# SheetV1.net
KiCad netlist of a schematic drawn in Altium Designer
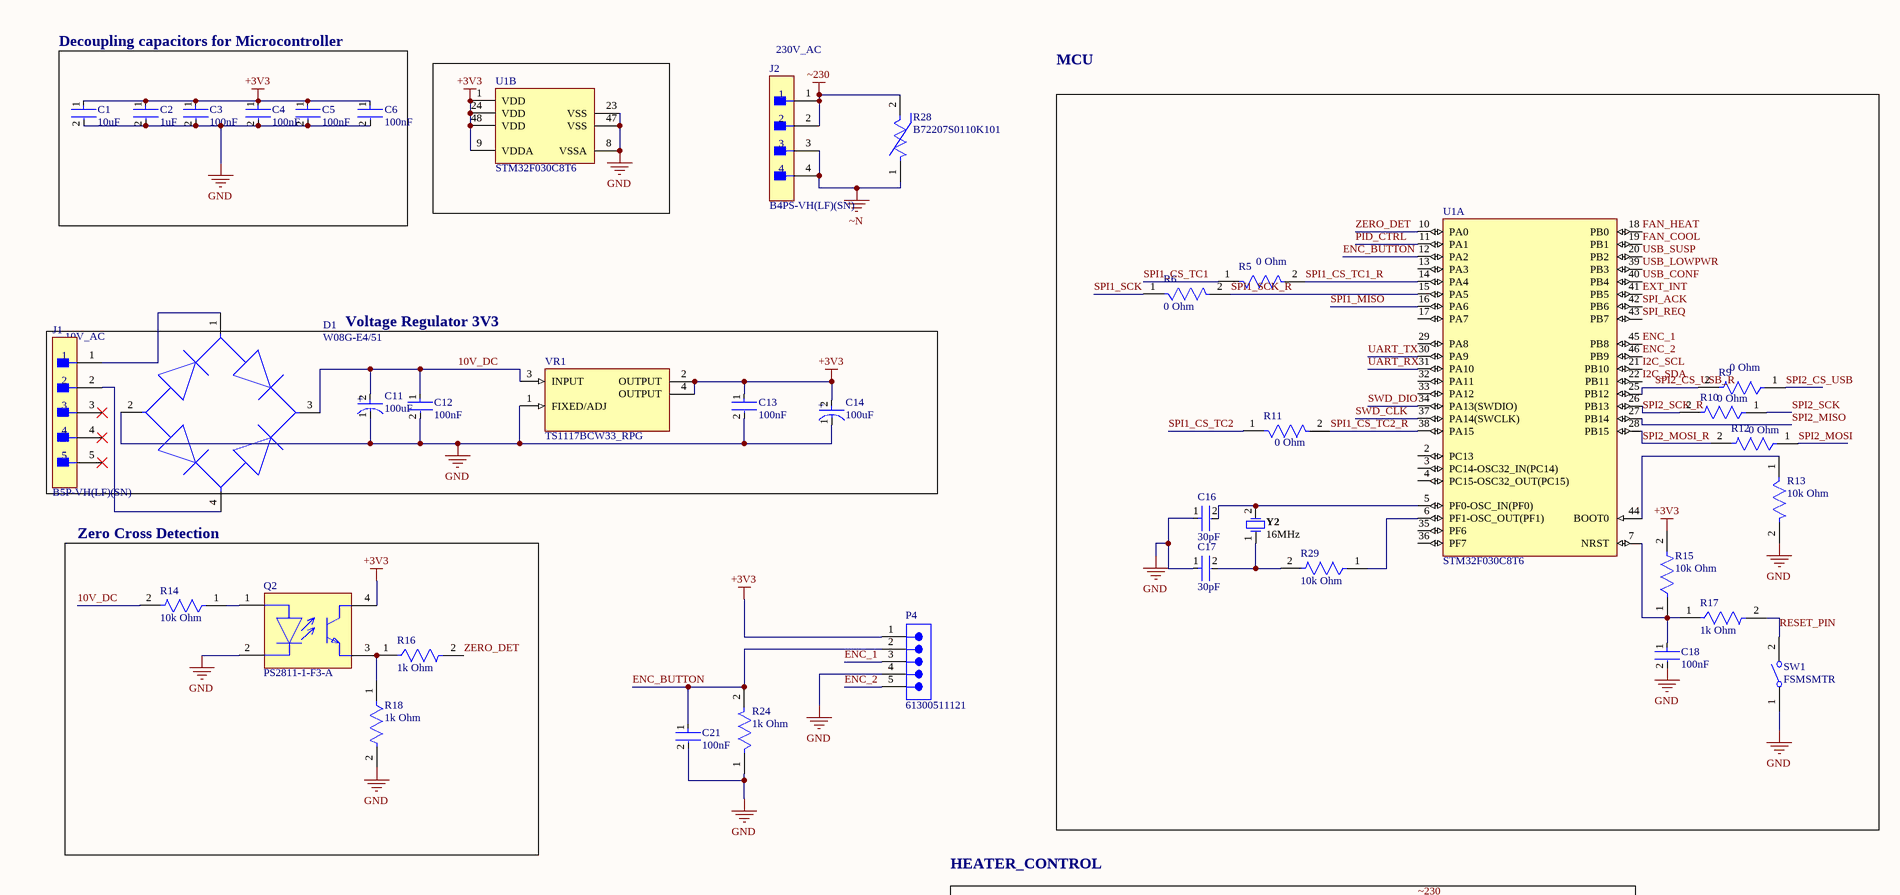
[diagram p0: SheetV1.SchDoc, top left]
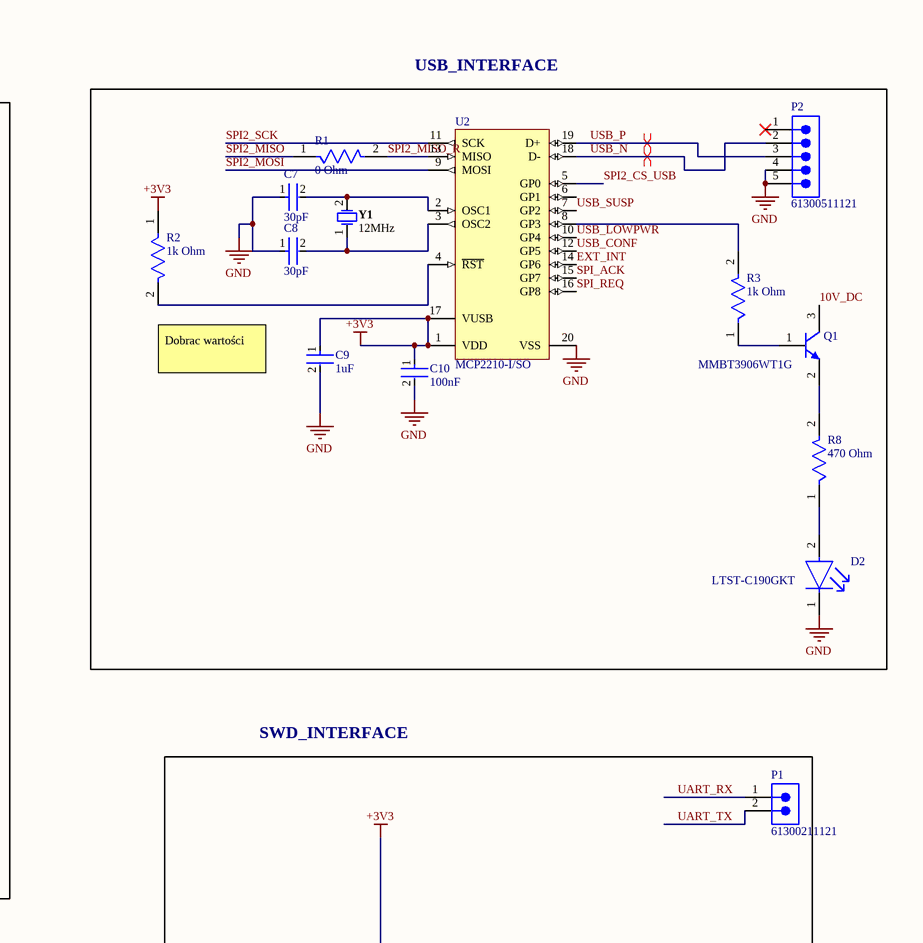
[diagram p1: SheetV1.SchDoc, top right]
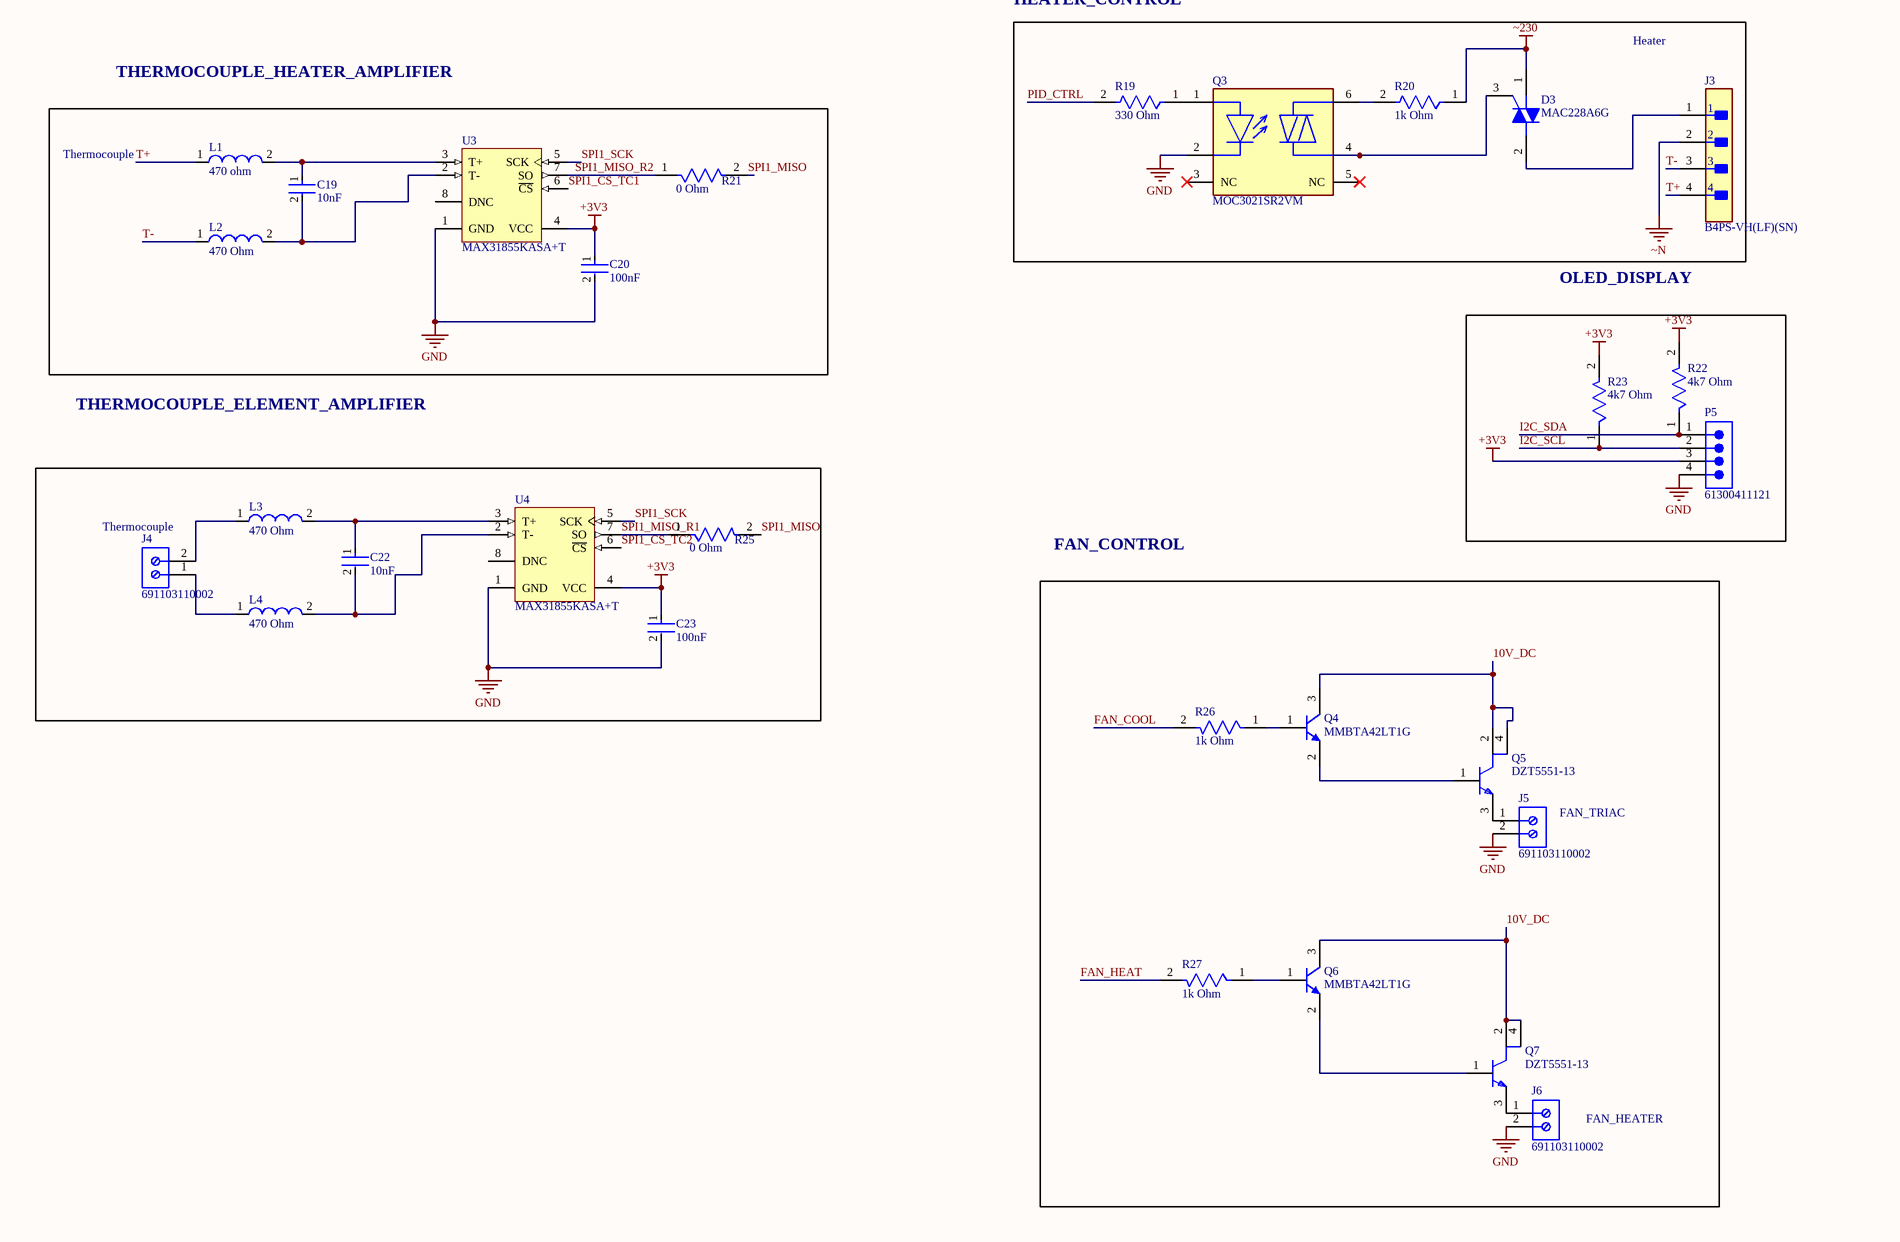
[diagram p2: SheetV1.SchDoc, bottom left]
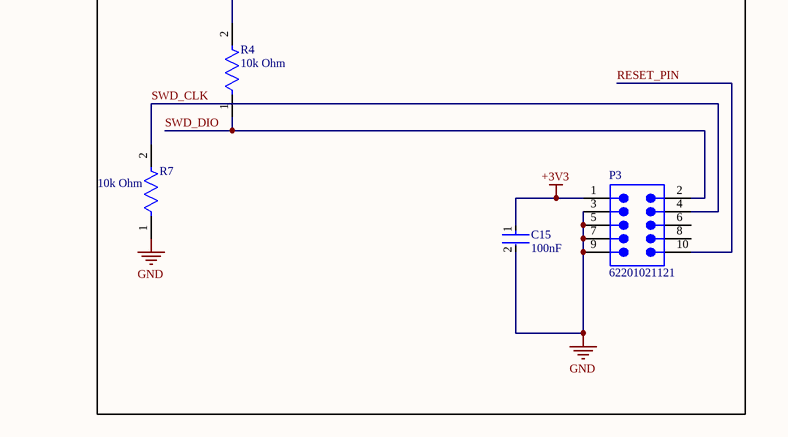
[diagram p3: SheetV1.SchDoc, bottom right]

(export (version "E")
  (design (tool "Eeschema 10.0.6"))
  (components
    (comp (ref "C1")
      (value "10uF")
      (footprint "FP-CC0805-0_85-MFG")
      (description "CAP CER 0.1UF 50V X7R 0805")
      (fields (field (name "TOLERANCE") "0.1") (field (name "MANUFACTURER PART NUMBER") "CC0805KRX7R9BB104"))
      (libsource (lib "Altium Content Vault") (part "11868f565c42a9108669ba33697ecf6"))
    )
    (comp (ref "C2")
      (value "1uF")
      (footprint "FP-CC0805-0_85-MFG")
      (description "CAP CER 0.1UF 50V X7R 0805")
      (fields (field (name "TOLERANCE") "0.1") (field (name "MANUFACTURER PART NUMBER") "CC0805KRX7R9BB104"))
      (libsource (lib "Altium Content Vault") (part "11868f565c42a9108669ba33697ecf6"))
    )
    (comp (ref "C3")
      (value "100nF")
      (footprint "FP-CC0805-0_85-MFG")
      (description "CAP CER 0.1UF 50V X7R 0805")
      (fields (field (name "TOLERANCE") "0.1") (field (name "MANUFACTURER PART NUMBER") "CC0805KRX7R9BB104"))
      (libsource (lib "Altium Content Vault") (part "11868f565c42a9108669ba33697ecf6"))
    )
    (comp (ref "C4")
      (value "100nF")
      (footprint "FP-CC0805-0_85-MFG")
      (description "CAP CER 0.1UF 50V X7R 0805")
      (fields (field (name "TOLERANCE") "0.1") (field (name "MANUFACTURER PART NUMBER") "CC0805KRX7R9BB104"))
      (libsource (lib "Altium Content Vault") (part "11868f565c42a9108669ba33697ecf6"))
    )
    (comp (ref "C5")
      (value "100nF")
      (footprint "FP-CC0805-0_85-MFG")
      (description "CAP CER 0.1UF 50V X7R 0805")
      (fields (field (name "TOLERANCE") "0.1") (field (name "MANUFACTURER PART NUMBER") "CC0805KRX7R9BB104"))
      (libsource (lib "Altium Content Vault") (part "11868f565c42a9108669ba33697ecf6"))
    )
    (comp (ref "C6")
      (value "100nF")
      (footprint "FP-CC0805-0_85-MFG")
      (description "CAP CER 0.1UF 50V X7R 0805")
      (fields (field (name "TOLERANCE") "0.1") (field (name "MANUFACTURER PART NUMBER") "CC0805KRX7R9BB104"))
      (libsource (lib "Altium Content Vault") (part "11868f565c42a9108669ba33697ecf6"))
    )
    (comp (ref "C7")
      (value "30pF")
      (footprint "FP-CC0805-0_85-MFG")
      (description "CAP CER 0.1UF 50V X7R 0805")
      (fields (field (name "TOLERANCE") "0.1") (field (name "MANUFACTURER PART NUMBER") "CC0805KRX7R9BB104"))
      (libsource (lib "Altium Content Vault") (part "11868f565c42a9108669ba33697ecf6"))
    )
    (comp (ref "C8")
      (value "30pF")
      (footprint "FP-CC0805-0_85-MFG")
      (description "CAP CER 0.1UF 50V X7R 0805")
      (fields (field (name "TOLERANCE") "0.1") (field (name "MANUFACTURER PART NUMBER") "CC0805KRX7R9BB104"))
      (libsource (lib "Altium Content Vault") (part "11868f565c42a9108669ba33697ecf6"))
    )
    (comp (ref "C9")
      (value "1uF")
      (footprint "FP-CC0805-0_85-MFG")
      (description "CAP CER 0.1UF 50V X7R 0805")
      (fields (field (name "TOLERANCE") "0.1") (field (name "MANUFACTURER PART NUMBER") "CC0805KRX7R9BB104"))
      (libsource (lib "Altium Content Vault") (part "11868f565c42a9108669ba33697ecf6"))
    )
    (comp (ref "C10")
      (value "100nF")
      (footprint "FP-CC0805-0_85-MFG")
      (description "CAP CER 0.1UF 50V X7R 0805")
      (fields (field (name "TOLERANCE") "0.1") (field (name "MANUFACTURER PART NUMBER") "CC0805KRX7R9BB104"))
      (libsource (lib "Altium Content Vault") (part "11868f565c42a9108669ba33697ecf6"))
    )
    (comp (ref "C11")
      (value "100uF")
      (footprint "FP-RAD-TH-D_10_0_5-L_12_5-MFG")
      (description "Aluminum Electrolytic Capacitors (Radial Lead Type) 3.3uF ±20% 400V")
      (fields (field (name "TOLERANCE") "20%") (field (name "VOLTAGE") "400V"))
      (libsource (lib "Altium Content Vault") (part "203bc49f2ac43e59fd269a8c329ed05"))
    )
    (comp (ref "C12")
      (value "100nF")
      (footprint "FP-CC0805-0_85-MFG")
      (description "CAP CER 0.1UF 50V X7R 0805")
      (fields (field (name "TOLERANCE") "0.1") (field (name "MANUFACTURER PART NUMBER") "CC0805KRX7R9BB104"))
      (libsource (lib "Altium Content Vault") (part "11868f565c42a9108669ba33697ecf6"))
    )
    (comp (ref "C13")
      (value "100nF")
      (footprint "FP-CC0805-0_85-MFG")
      (description "CAP CER 0.1UF 50V X7R 0805")
      (fields (field (name "TOLERANCE") "0.1") (field (name "MANUFACTURER PART NUMBER") "CC0805KRX7R9BB104"))
      (libsource (lib "Altium Content Vault") (part "11868f565c42a9108669ba33697ecf6"))
    )
    (comp (ref "C14")
      (value "100uF")
      (footprint "FP-RAD-TH-D_10_0_5-L_12_5-MFG")
      (description "Aluminum Electrolytic Capacitors (Radial Lead Type) 3.3uF ±20% 400V")
      (fields (field (name "TOLERANCE") "20%") (field (name "VOLTAGE") "400V"))
      (libsource (lib "Altium Content Vault") (part "203bc49f2ac43e59fd269a8c329ed05"))
    )
    (comp (ref "C15")
      (value "100nF")
      (footprint "FP-CC0805-0_85-MFG")
      (description "CAP CER 0.1UF 50V X7R 0805")
      (fields (field (name "TOLERANCE") "0.1") (field (name "MANUFACTURER PART NUMBER") "CC0805KRX7R9BB104"))
      (libsource (lib "Altium Content Vault") (part "11868f565c42a9108669ba33697ecf6"))
    )
    (comp (ref "C16")
      (value "30pF")
      (footprint "FP-CC0805-0_85-MFG")
      (description "CAP CER 0.1UF 50V X7R 0805")
      (fields (field (name "TOLERANCE") "0.1") (field (name "MANUFACTURER PART NUMBER") "CC0805KRX7R9BB104"))
      (libsource (lib "Altium Content Vault") (part "11868f565c42a9108669ba33697ecf6"))
    )
    (comp (ref "C17")
      (value "30pF")
      (footprint "FP-CC0805-0_85-MFG")
      (description "CAP CER 0.1UF 50V X7R 0805")
      (fields (field (name "TOLERANCE") "0.1") (field (name "MANUFACTURER PART NUMBER") "CC0805KRX7R9BB104"))
      (libsource (lib "Altium Content Vault") (part "11868f565c42a9108669ba33697ecf6"))
    )
    (comp (ref "C18")
      (value "100nF")
      (footprint "FP-CC0805-0_85-MFG")
      (description "CAP CER 0.1UF 50V X7R 0805")
      (fields (field (name "TOLERANCE") "0.1") (field (name "MANUFACTURER PART NUMBER") "CC0805KRX7R9BB104"))
      (libsource (lib "Altium Content Vault") (part "11868f565c42a9108669ba33697ecf6"))
    )
    (comp (ref "C19")
      (value "10nF")
      (footprint "FP-CC0805-0_85-MFG")
      (description "CAP CER 0.1UF 50V X7R 0805")
      (fields (field (name "TOLERANCE") "0.1") (field (name "MANUFACTURER PART NUMBER") "CC0805KRX7R9BB104"))
      (libsource (lib "Altium Content Vault") (part "11868f565c42a9108669ba33697ecf6"))
    )
    (comp (ref "C20")
      (value "100nF")
      (footprint "FP-CC0805-0_85-MFG")
      (description "CAP CER 0.1UF 50V X7R 0805")
      (fields (field (name "TOLERANCE") "0.1") (field (name "MANUFACTURER PART NUMBER") "CC0805KRX7R9BB104"))
      (libsource (lib "Altium Content Vault") (part "11868f565c42a9108669ba33697ecf6"))
    )
    (comp (ref "C21")
      (value "100nF")
      (footprint "FP-CC0805-0_85-MFG")
      (description "CAP CER 0.1UF 50V X7R 0805")
      (fields (field (name "TOLERANCE") "0.1") (field (name "MANUFACTURER PART NUMBER") "CC0805KRX7R9BB104"))
      (libsource (lib "Altium Content Vault") (part "11868f565c42a9108669ba33697ecf6"))
    )
    (comp (ref "C22")
      (value "10nF")
      (footprint "FP-CC0805-0_85-MFG")
      (description "CAP CER 0.1UF 50V X7R 0805")
      (fields (field (name "TOLERANCE") "0.1") (field (name "MANUFACTURER PART NUMBER") "CC0805KRX7R9BB104"))
      (libsource (lib "Altium Content Vault") (part "11868f565c42a9108669ba33697ecf6"))
    )
    (comp (ref "C23")
      (value "100nF")
      (footprint "FP-CC0805-0_85-MFG")
      (description "CAP CER 0.1UF 50V X7R 0805")
      (fields (field (name "TOLERANCE") "0.1") (field (name "MANUFACTURER PART NUMBER") "CC0805KRX7R9BB104"))
      (libsource (lib "Altium Content Vault") (part "11868f565c42a9108669ba33697ecf6"))
    )
    (comp (ref "D1")
      (value "W08G-E4/51")
      (footprint "FP-WOG-MFG")
      (description "W08G-E4/51 Diode Rectifier Bridge Single 800V 1.5A 4-Pin Case WOG Bulk")
      (libsource (lib "Altium Content Vault") (part "7f679ecdc54638986ed3433d0c5b104"))
    )
    (comp (ref "D2")
      (value "LTST-C190GKT")
      (footprint "FP-LTST-C190GKT-MFG")
      (description "LED GREEN CLEAR CHIP SMD")
      (fields (field (name "VOLTAGE") "2V"))
      (libsource (lib "Altium Content Vault") (part "8706943c75ba83719d021d2fdc84c58"))
    )
    (comp (ref "D3")
      (value "MAC228A6G")
      (footprint "ONSC-TO-220-3-221A-09")
      (description "Sensitive Gate Triacs, Silicon Bidirectional Thyristor, 3-Pin TO-220, Pb-Free, Bulk Box")
      (fields (field (name "MANUFACTURER") "On Semiconductor"))
      (libsource (lib "Altium Content Vault") (part "ONSC-TRIAC-MT1MT2G-3"))
    )
    (comp (ref "J1")
      (value "B5P-VH(LF)(SN)")
      (footprint "FP-B5P-VH_LF_SN-MFG")
      (description "CONN HEADER VERT 5POS 3.96MM")
      (libsource (lib "Altium Content Vault") (part "051ac7c1f60a91215dd69c4e70fad1a"))
    )
    (comp (ref "J2")
      (value "B4PS-VH(LF)(SN)")
      (footprint "FP-B4PS-VH_LF_SN-MFG")
      (description "CONN HEADER R/A 4POS 3.96MM")
      (libsource (lib "") (part "299a8cea1bdcbc3624fe62c390fa72c_1"))
    )
    (comp (ref "J3")
      (value "B4PS-VH(LF)(SN)")
      (footprint "FP-B4PS-VH_LF_SN-MFG")
      (description "CONN HEADER R/A 4POS 3.96MM")
      (libsource (lib "Altium Content Vault") (part "299a8cea1bdcbc3624fe62c390fa72c"))
    )
    (comp (ref "J4")
      (value "691103110002")
      (footprint "691103110002")
      (fields (field (name "VOLTAGE") "125V"))
      (libsource (lib "Altium Content Vault") (part "TBL - 1R - 02P - Screw"))
    )
    (comp (ref "J5")
      (value "691103110002")
      (footprint "691103110002")
      (fields (field (name "VOLTAGE") "125V"))
      (libsource (lib "Altium Content Vault") (part "TBL - 1R - 02P - Screw"))
    )
    (comp (ref "J6")
      (value "691103110002")
      (footprint "691103110002")
      (fields (field (name "VOLTAGE") "125V"))
      (libsource (lib "Altium Content Vault") (part "TBL - 1R - 02P - Screw"))
    )
    (comp (ref "L1")
      (value "470 ohm")
      (footprint "SMD-0805")
      (description "SMD EMI Suppression Ferrite Bead WE-CBF, Z = 470 Ohm")
      (libsource (lib "Altium Content Vault") (part "PAS-IND-INDUCTOR-2"))
    )
    (comp (ref "L2")
      (value "470 Ohm")
      (footprint "SMD-0805")
      (description "SMD EMI Suppression Ferrite Bead WE-CBF, Z = 470 Ohm")
      (libsource (lib "Altium Content Vault") (part "PAS-IND-INDUCTOR-2"))
    )
    (comp (ref "L3")
      (value "470 Ohm")
      (footprint "SMD-0805")
      (description "SMD EMI Suppression Ferrite Bead WE-CBF, Z = 470 Ohm")
      (libsource (lib "Altium Content Vault") (part "PAS-IND-INDUCTOR-2"))
    )
    (comp (ref "L4")
      (value "470 Ohm")
      (footprint "SMD-0805")
      (description "SMD EMI Suppression Ferrite Bead WE-CBF, Z = 470 Ohm")
      (libsource (lib "Altium Content Vault") (part "PAS-IND-INDUCTOR-2"))
    )
    (comp (ref "P1")
      (value "61300211121")
      (footprint "61300211121")
      (libsource (lib "Altium Content Vault") (part "Header_Male_1R_02P"))
    )
    (comp (ref "P2")
      (value "61300511121")
      (footprint "61300511121")
      (libsource (lib "Altium Content Vault") (part "Header_Male_1R_05P"))
    )
    (comp (ref "P3")
      (value "62201021121")
      (footprint "62201021121")
      (libsource (lib "Altium Content Vault") (part "Header_Male_2R_10P"))
    )
    (comp (ref "P4")
      (value "61300511121")
      (footprint "61300511121")
      (libsource (lib "Altium Content Vault") (part "Header_Male_1R_05P"))
    )
    (comp (ref "P5")
      (value "61300411121")
      (footprint "61300411121")
      (libsource (lib "Altium Content Vault") (part "Header_Male_1R_04P"))
    )
    (comp (ref "Q1")
      (value "MMBT3906WT1G")
      (footprint "ONSC-SC-70-3-419-04_V")
      (description "General Purpose Transistor, PNP Silicon, 3-Pin SC70, Pb-Free, Tape and Reel")
      (fields (field (name "MANUFACTURER") "On Semiconductor"))
      (libsource (lib "Altium Content Vault") (part "ONSC-NPN-B1E2C3-3"))
    )
    (comp (ref "Q2")
      (value "PS2811-1-F3-A")
      (footprint "SOP127P700X210_HS-5_SO4-Opto2_N")
      (description "Optocoupler DC-IN 1-CH Transistor DC-OUT 4-Pin SSOP Embossed T/R")
      (libsource (lib "Altium Content Vault") (part "f4732c5a005c16655bf03302f8bd1cc"))
    )
    (comp (ref "Q3")
      (value "MOC3021SR2VM")
      (footprint "FP-646BY-MFG")
      (description "MOC3021SR2VM Triac Driver Output Optocoupler, 6-Pin DIP 400V Random Phase")
      (libsource (lib "Altium Content Vault") (part "315d33d7a3de83856d3bd334bf87c2f"))
    )
    (comp (ref "Q4")
      (value "MMBTA42LT1G")
      (footprint "ONSC-SOT-23-3-318-08_V")
      (description "High Voltage Transistor, NPN Silicon, 3-Pin SOT-23, Pb-Free, Tape and Reel")
      (fields (field (name "MANUFACTURER") "On Semiconductor"))
      (libsource (lib "Altium Content Vault") (part "ONSC-NPN-B1E2C3-3"))
    )
    (comp (ref "Q5")
      (value "DZT5551-13")
      (footprint "FP-SOT223-MFG")
      (description "TRANS NPN 160V 0.6A SOT-223")
      (fields
        (field (name "MANUFACTURER") "Diodes")
        (field (name "OCTOPART") "https://octopart.com/dzt5551-13-diodes+inc.-12426785")
      )
      (libsource (lib "Altium Content Vault") (part "ef0222921274e2dfe3c88fb5f98777d"))
    )
    (comp (ref "Q6")
      (value "MMBTA42LT1G")
      (footprint "ONSC-SOT-23-3-318-08_V")
      (description "High Voltage Transistor, NPN Silicon, 3-Pin SOT-23, Pb-Free, Tape and Reel")
      (fields (field (name "MANUFACTURER") "On Semiconductor"))
      (libsource (lib "Altium Content Vault") (part "ONSC-NPN-B1E2C3-3"))
    )
    (comp (ref "Q7")
      (value "DZT5551-13")
      (footprint "FP-SOT223-MFG")
      (description "TRANS NPN 160V 0.6A SOT-223")
      (fields
        (field (name "MANUFACTURER") "Diodes")
        (field (name "OCTOPART") "https://octopart.com/dzt5551-13-diodes+inc.-12426785")
      )
      (libsource (lib "Altium Content Vault") (part "ef0222921274e2dfe3c88fb5f98777d"))
    )
    (comp (ref "R1")
      (value "0 Ohm")
      (footprint "FP-RMCF0805-MFG")
      (description "RES 0 OHM JUMPER 1/8W 0805")
      (libsource (lib "Altium Content Vault") (part "1029c3af85768c4190bb7ad29bc67b5"))
    )
    (comp (ref "R2")
      (value "1k Ohm")
      (footprint "FP-RMCF0805-MFG")
      (description "RES 0 OHM JUMPER 1/8W 0805")
      (libsource (lib "Altium Content Vault") (part "1029c3af85768c4190bb7ad29bc67b5"))
    )
    (comp (ref "R3")
      (value "1k Ohm")
      (footprint "FP-RMCF0805-MFG")
      (description "RES 0 OHM JUMPER 1/8W 0805")
      (libsource (lib "Altium Content Vault") (part "1029c3af85768c4190bb7ad29bc67b5"))
    )
    (comp (ref "R4")
      (value "10k Ohm")
      (footprint "FP-RMCF0805-MFG")
      (description "RES 0 OHM JUMPER 1/8W 0805")
      (libsource (lib "Altium Content Vault") (part "1029c3af85768c4190bb7ad29bc67b5"))
    )
    (comp (ref "R5")
      (value "0 Ohm")
      (footprint "FP-RMCF0805-MFG")
      (description "RES 0 OHM JUMPER 1/8W 0805")
      (libsource (lib "Altium Content Vault") (part "1029c3af85768c4190bb7ad29bc67b5"))
    )
    (comp (ref "R6")
      (value "0 Ohm")
      (footprint "FP-RMCF0805-MFG")
      (description "RES 0 OHM JUMPER 1/8W 0805")
      (libsource (lib "Altium Content Vault") (part "1029c3af85768c4190bb7ad29bc67b5"))
    )
    (comp (ref "R7")
      (value "10k Ohm")
      (footprint "FP-RMCF0805-MFG")
      (description "RES 0 OHM JUMPER 1/8W 0805")
      (libsource (lib "Altium Content Vault") (part "1029c3af85768c4190bb7ad29bc67b5"))
    )
    (comp (ref "R8")
      (value "470 Ohm")
      (footprint "FP-RMCF0805-MFG")
      (description "RES 0 OHM JUMPER 1/8W 0805")
      (libsource (lib "Altium Content Vault") (part "1029c3af85768c4190bb7ad29bc67b5"))
    )
    (comp (ref "R9")
      (value "0 Ohm")
      (footprint "FP-RMCF0805-MFG")
      (description "RES 0 OHM JUMPER 1/8W 0805")
      (libsource (lib "Altium Content Vault") (part "1029c3af85768c4190bb7ad29bc67b5"))
    )
    (comp (ref "R10")
      (value "0 Ohm")
      (footprint "FP-RMCF0805-MFG")
      (description "RES 0 OHM JUMPER 1/8W 0805")
      (libsource (lib "Altium Content Vault") (part "1029c3af85768c4190bb7ad29bc67b5"))
    )
    (comp (ref "R11")
      (value "0 Ohm")
      (footprint "FP-RMCF0805-MFG")
      (description "RES 0 OHM JUMPER 1/8W 0805")
      (libsource (lib "Altium Content Vault") (part "1029c3af85768c4190bb7ad29bc67b5"))
    )
    (comp (ref "R12")
      (value "0 Ohm")
      (footprint "FP-RMCF0805-MFG")
      (description "RES 0 OHM JUMPER 1/8W 0805")
      (libsource (lib "Altium Content Vault") (part "1029c3af85768c4190bb7ad29bc67b5"))
    )
    (comp (ref "R13")
      (value "10k Ohm")
      (footprint "FP-RMCF0805-MFG")
      (description "RES 0 OHM JUMPER 1/8W 0805")
      (libsource (lib "Altium Content Vault") (part "1029c3af85768c4190bb7ad29bc67b5"))
    )
    (comp (ref "R14")
      (value "10k Ohm")
      (footprint "FP-RMCF0805-MFG")
      (description "RES 0 OHM JUMPER 1/8W 0805")
      (libsource (lib "Altium Content Vault") (part "1029c3af85768c4190bb7ad29bc67b5"))
    )
    (comp (ref "R15")
      (value "10k Ohm")
      (footprint "FP-RMCF0805-MFG")
      (description "RES 0 OHM JUMPER 1/8W 0805")
      (libsource (lib "Altium Content Vault") (part "1029c3af85768c4190bb7ad29bc67b5"))
    )
    (comp (ref "R16")
      (value "1k Ohm")
      (footprint "FP-RMCF0805-MFG")
      (description "RES 0 OHM JUMPER 1/8W 0805")
      (libsource (lib "Altium Content Vault") (part "1029c3af85768c4190bb7ad29bc67b5"))
    )
    (comp (ref "R17")
      (value "1k Ohm")
      (footprint "FP-RMCF0805-MFG")
      (description "RES 0 OHM JUMPER 1/8W 0805")
      (libsource (lib "Altium Content Vault") (part "1029c3af85768c4190bb7ad29bc67b5"))
    )
    (comp (ref "R18")
      (value "1k Ohm")
      (footprint "FP-RMCF0805-MFG")
      (description "RES 0 OHM JUMPER 1/8W 0805")
      (libsource (lib "Altium Content Vault") (part "1029c3af85768c4190bb7ad29bc67b5"))
    )
    (comp (ref "R19")
      (value "330 Ohm")
      (footprint "FP-RMCF0805-MFG")
      (description "RES 0 OHM JUMPER 1/8W 0805")
      (libsource (lib "Altium Content Vault") (part "1029c3af85768c4190bb7ad29bc67b5"))
    )
    (comp (ref "R20")
      (value "1k Ohm")
      (footprint "FP-RMCF0805-MFG")
      (description "RES 0 OHM JUMPER 1/8W 0805")
      (libsource (lib "Altium Content Vault") (part "1029c3af85768c4190bb7ad29bc67b5"))
    )
    (comp (ref "R21")
      (value "0 Ohm")
      (footprint "FP-RMCF0805-MFG")
      (description "RES 0 OHM JUMPER 1/8W 0805")
      (libsource (lib "Altium Content Vault") (part "1029c3af85768c4190bb7ad29bc67b5"))
    )
    (comp (ref "R22")
      (value "4k7 Ohm")
      (footprint "FP-RMCF0805-MFG")
      (description "RES 0 OHM JUMPER 1/8W 0805")
      (libsource (lib "Altium Content Vault") (part "1029c3af85768c4190bb7ad29bc67b5"))
    )
    (comp (ref "R23")
      (value "4k7 Ohm")
      (footprint "FP-RMCF0805-MFG")
      (description "RES 0 OHM JUMPER 1/8W 0805")
      (libsource (lib "Altium Content Vault") (part "1029c3af85768c4190bb7ad29bc67b5"))
    )
    (comp (ref "R24")
      (value "1k Ohm")
      (footprint "FP-RMCF0805-MFG")
      (description "RES 0 OHM JUMPER 1/8W 0805")
      (libsource (lib "Altium Content Vault") (part "1029c3af85768c4190bb7ad29bc67b5"))
    )
    (comp (ref "R25")
      (value "0 Ohm")
      (footprint "FP-RMCF0805-MFG")
      (description "RES 0 OHM JUMPER 1/8W 0805")
      (libsource (lib "Altium Content Vault") (part "1029c3af85768c4190bb7ad29bc67b5"))
    )
    (comp (ref "R26")
      (value "1k Ohm")
      (footprint "FP-RMCF0805-MFG")
      (description "RES 0 OHM JUMPER 1/8W 0805")
      (libsource (lib "Altium Content Vault") (part "1029c3af85768c4190bb7ad29bc67b5"))
    )
    (comp (ref "R27")
      (value "1k Ohm")
      (footprint "FP-RMCF0805-MFG")
      (description "RES 0 OHM JUMPER 1/8W 0805")
      (libsource (lib "Altium Content Vault") (part "1029c3af85768c4190bb7ad29bc67b5"))
    )
    (comp (ref "R28")
      (value "B72207S0110K101")
      (footprint "FP-B72207S0110K101-MFG")
      (description "VARISTOR 18V 250A DISC 7MM")
      (fields
        (field (name "MANUFACTURER") "EPCOS")
        (field (name "OCTOPART") "https://octopart.com/b72207s0110k101-epcos-11931358")
      )
      (libsource (lib "Altium Content Vault") (part "78a88060d5b7b043d6e48adc4284376"))
    )
    (comp (ref "R29")
      (value "10k Ohm")
      (footprint "FP-RMCF0805-MFG")
      (description "RES 0 OHM JUMPER 1/8W 0805")
      (libsource (lib "Altium Content Vault") (part "1029c3af85768c4190bb7ad29bc67b5"))
    )
    (comp (ref "SW1")
      (value "FSMSMTR")
      (footprint "TECO-FSMSMTR_V")
      (description "FSMSM Push Button Switch, 50 mA, -35 to 85 degC, 2-Pin SMD, RoHS, Tape and Reel")
      (fields (field (name "MANUFACTURER") "TE Connectivity"))
      (libsource (lib "Altium Content Vault") (part "SW-SPST-2_C"))
    )
    (comp (ref "U1")
      (value "STM32F030C8T6")
      (footprint "STM-LQFP48_M")
      (libsource (lib "Altium Content Vault") (part "MC-ARM-STM32F030_X8-SQ48"))
    )
    (comp (ref "U2")
      (value "MCP2210-I/SO")
      (footprint "SOIC-SO20_N")
      (description "USB-to-SPI Protocol Converter with GPIO (Master Mode), 20-Pin SOIC, Industrial Temperature")
      (libsource (lib "Altium Content Vault") (part "COM-USB-MCP2210-20"))
    )
    (comp (ref "U3")
      (value "MAX31855KASA+T")
      (footprint "MAXM-S8+4_N")
      (fields (field (name "GENERIC PART NUMBER") "MAX31855"))
      (libsource (lib "Altium Content Vault") (part "MAX31855-S8+4"))
    )
    (comp (ref "U4")
      (value "MAX31855KASA+T")
      (footprint "MAXM-S8+4_N")
      (fields (field (name "GENERIC PART NUMBER") "MAX31855"))
      (libsource (lib "Altium Content Vault") (part "MAX31855-S8+4"))
    )
    (comp (ref "VR1")
      (value "TS1117BCW33_RPG")
      (footprint "VREG_TS1117BCW50_RPG")
      (fields (field (name "MP") "TS1117BCW50_RPG"))
      (libsource (lib "TS1117BCW50_RPG") (part "TS1117BCW50_RPG"))
    )
    (comp (ref "Y1")
      (value "12MHz")
      (footprint "FOX-FOXSLF160-20")
      (description "Resistance Weld Thru-Hole Crystal, 16 MHz, -20 to 70 degC, 2-Pin THD, RoHS, Bulk")
      (fields (field (name "TOLERANCE") "1%"))
      (libsource (lib "Altium Content Vault") (part "XTAL-1-2-2"))
    )
    (comp (ref "Y2")
      (value "16MHz")
      (footprint "FOX-FOXSLF160-20")
      (description "Resistance Weld Thru-Hole Crystal, 16 MHz, -20 to 70 degC, 2-Pin THD, RoHS, Bulk")
      (fields (field (name "TOLERANCE") "1%"))
      (libsource (lib "Altium Content Vault") (part "XTAL-1-2-2"))
    )
  )
  (nets
    (net (code "1") (name "+3V3") (class "Default")
      (node (ref "C1") (pin "1") (pinfunction "1_1") (pintype "passive"))
      (node (ref "C10") (pin "1") (pinfunction "1_1") (pintype "passive"))
      (node (ref "C13") (pin "1") (pinfunction "1_1") (pintype "passive"))
      (node (ref "C14") (pin "2") (pinfunction "A_2") (pintype "passive"))
      (node (ref "C15") (pin "1") (pinfunction "1_1") (pintype "passive"))
      (node (ref "C2") (pin "1") (pinfunction "1_1") (pintype "passive"))
      (node (ref "C20") (pin "1") (pinfunction "1_1") (pintype "passive"))
      (node (ref "C23") (pin "1") (pinfunction "1_1") (pintype "passive"))
      (node (ref "C3") (pin "1") (pinfunction "1_1") (pintype "passive"))
      (node (ref "C4") (pin "1") (pinfunction "1_1") (pintype "passive"))
      (node (ref "C5") (pin "1") (pinfunction "1_1") (pintype "passive"))
      (node (ref "C6") (pin "1") (pinfunction "1_1") (pintype "passive"))
      (node (ref "C9") (pin "1") (pinfunction "1_1") (pintype "passive"))
      (node (ref "P3") (pin "1") (pinfunction "1_1") (pintype "passive"))
      (node (ref "P4") (pin "1") (pinfunction "1_1") (pintype "passive"))
      (node (ref "P5") (pin "3") (pinfunction "3_3") (pintype "passive"))
      (node (ref "Q2") (pin "4") (pinfunction "C_4") (pintype "passive"))
      (node (ref "R15") (pin "2") (pinfunction "2_2") (pintype "passive"))
      (node (ref "R2") (pin "1") (pinfunction "1_1") (pintype "passive"))
      (node (ref "R22") (pin "2") (pinfunction "2_2") (pintype "passive"))
      (node (ref "R23") (pin "2") (pinfunction "2_2") (pintype "passive"))
      (node (ref "R4") (pin "2") (pinfunction "2_2") (pintype "passive"))
      (node (ref "U1") (pin "1") (pinfunction "VDD_1") (pintype "power_in"))
      (node (ref "U1") (pin "24") (pinfunction "VDD_24") (pintype "power_in"))
      (node (ref "U1") (pin "48") (pinfunction "VDD_48") (pintype "power_in"))
      (node (ref "U1") (pin "9") (pinfunction "VDDA_9") (pintype "power_in"))
      (node (ref "U2") (pin "1") (pinfunction "VDD_1") (pintype "power_in"))
      (node (ref "U2") (pin "17") (pinfunction "VUSB_17") (pintype "power_in"))
      (node (ref "U3") (pin "4") (pinfunction "VCC_4") (pintype "power_in"))
      (node (ref "U4") (pin "4") (pinfunction "VCC_4") (pintype "power_in"))
      (node (ref "VR1") (pin "2") (pinfunction "OUTPUT_2") (pintype "power_in"))
      (node (ref "VR1") (pin "4") (pinfunction "OUTPUT_4") (pintype "power_in"))
    )
    (net (code "2") (name "/10V_DC") (class "Default")
      (node (ref "C11") (pin "2") (pinfunction "A_2") (pintype "passive"))
      (node (ref "C12") (pin "1") (pinfunction "1_1") (pintype "passive"))
      (node (ref "D1") (pin "3") (pinfunction "-_3") (pintype "passive"))
      (node (ref "Q1") (pin "3") (pinfunction "C_3") (pintype "passive"))
      (node (ref "Q4") (pin "3") (pinfunction "C_3") (pintype "passive"))
      (node (ref "Q5") (pin "2") (pinfunction "C_2") (pintype "passive"))
      (node (ref "Q5") (pin "4") (pinfunction "C_4") (pintype "passive"))
      (node (ref "Q6") (pin "3") (pinfunction "C_3") (pintype "passive"))
      (node (ref "Q7") (pin "2") (pinfunction "C_2") (pintype "passive"))
      (node (ref "Q7") (pin "4") (pinfunction "C_4") (pintype "passive"))
      (node (ref "R14") (pin "2") (pinfunction "2_2") (pintype "passive"))
      (node (ref "VR1") (pin "3") (pinfunction "INPUT_3") (pintype "input"))
    )
    (net (code "3") (name "/ENC_1") (class "Default")
      (node (ref "P4") (pin "3") (pinfunction "3_3") (pintype "passive"))
      (node (ref "U1") (pin "45") (pinfunction "PB8_45") (pintype "bidirectional"))
    )
    (net (code "4") (name "/ENC_2") (class "Default")
      (node (ref "P4") (pin "5") (pinfunction "5_5") (pintype "passive"))
      (node (ref "U1") (pin "46") (pinfunction "PB9_46") (pintype "bidirectional"))
    )
    (net (code "5") (name "/ENC_BUTTON") (class "Default")
      (node (ref "C21") (pin "1") (pinfunction "1_1") (pintype "passive"))
      (node (ref "P4") (pin "2") (pinfunction "2_2") (pintype "passive"))
      (node (ref "R24") (pin "2") (pinfunction "2_2") (pintype "passive"))
      (node (ref "U1") (pin "12") (pinfunction "PA2_12") (pintype "bidirectional"))
    )
    (net (code "6") (name "/EXT_INT") (class "Default")
      (node (ref "U1") (pin "41") (pinfunction "PB5_41") (pintype "bidirectional"))
      (node (ref "U2") (pin "14") (pinfunction "GP6_14") (pintype "bidirectional"))
    )
    (net (code "7") (name "/FAN_COOL") (class "Default")
      (node (ref "R26") (pin "2") (pinfunction "2_2") (pintype "passive"))
      (node (ref "U1") (pin "19") (pinfunction "PB1_19") (pintype "bidirectional"))
    )
    (net (code "8") (name "/FAN_HEAT") (class "Default")
      (node (ref "R27") (pin "2") (pinfunction "2_2") (pintype "passive"))
      (node (ref "U1") (pin "18") (pinfunction "PB0_18") (pintype "bidirectional"))
    )
    (net (code "9") (name "/I2C_SCL") (class "Default")
      (node (ref "P5") (pin "2") (pinfunction "2_2") (pintype "passive"))
      (node (ref "R23") (pin "1") (pinfunction "1_1") (pintype "passive"))
      (node (ref "U1") (pin "21") (pinfunction "PB10_21") (pintype "bidirectional"))
    )
    (net (code "10") (name "/I2C_SDA") (class "Default")
      (node (ref "P5") (pin "1") (pinfunction "1_1") (pintype "passive"))
      (node (ref "R22") (pin "1") (pinfunction "1_1") (pintype "passive"))
      (node (ref "U1") (pin "22") (pinfunction "PB11_22") (pintype "bidirectional"))
    )
    (net (code "11") (name "/PID_CTRL") (class "Default")
      (node (ref "R19") (pin "2") (pinfunction "2_2") (pintype "passive"))
      (node (ref "U1") (pin "11") (pinfunction "PA1_11") (pintype "bidirectional"))
    )
    (net (code "12") (name "/RESET_PIN") (class "Default")
      (node (ref "P3") (pin "10") (pinfunction "10_10") (pintype "passive"))
      (node (ref "R17") (pin "2") (pinfunction "2_2") (pintype "passive"))
      (node (ref "SW1") (pin "2") (pinfunction "2_2") (pintype "passive"))
    )
    (net (code "13") (name "/SPI1_CS_TC1") (class "Default")
      (node (ref "R5") (pin "1") (pinfunction "1_1") (pintype "passive"))
      (node (ref "U3") (pin "6") (pinfunction "~{CS}_6") (pintype "input"))
    )
    (net (code "14") (name "/SPI1_CS_TC1_R") (class "Default")
      (node (ref "R5") (pin "2") (pinfunction "2_2") (pintype "passive"))
      (node (ref "U1") (pin "14") (pinfunction "PA4_14") (pintype "bidirectional"))
    )
    (net (code "15") (name "/SPI1_CS_TC2") (class "Default")
      (node (ref "R11") (pin "1") (pinfunction "1_1") (pintype "passive"))
      (node (ref "U4") (pin "6") (pinfunction "~{CS}_6") (pintype "input"))
    )
    (net (code "16") (name "/SPI1_CS_TC2_R") (class "Default")
      (node (ref "R11") (pin "2") (pinfunction "2_2") (pintype "passive"))
      (node (ref "U1") (pin "38") (pinfunction "PA15_38") (pintype "bidirectional"))
    )
    (net (code "17") (name "/SPI1_MISO") (class "Default")
      (node (ref "R21") (pin "2") (pinfunction "2_2") (pintype "passive"))
      (node (ref "R25") (pin "2") (pinfunction "2_2") (pintype "passive"))
      (node (ref "U1") (pin "16") (pinfunction "PA6_16") (pintype "bidirectional"))
    )
    (net (code "18") (name "/SPI1_MISO_R1") (class "Default")
      (node (ref "R25") (pin "1") (pinfunction "1_1") (pintype "passive"))
      (node (ref "U4") (pin "7") (pinfunction "SO_7") (pintype "output"))
    )
    (net (code "19") (name "/SPI1_MISO_R2") (class "Default")
      (node (ref "R21") (pin "1") (pinfunction "1_1") (pintype "passive"))
      (node (ref "U3") (pin "7") (pinfunction "SO_7") (pintype "output"))
    )
    (net (code "20") (name "/SPI1_SCK") (class "Default")
      (node (ref "R6") (pin "1") (pinfunction "1_1") (pintype "passive"))
      (node (ref "U3") (pin "5") (pinfunction "SCK_5") (pintype "input"))
      (node (ref "U4") (pin "5") (pinfunction "SCK_5") (pintype "input"))
    )
    (net (code "21") (name "/SPI1_SCK_R") (class "Default")
      (node (ref "R6") (pin "2") (pinfunction "2_2") (pintype "passive"))
      (node (ref "U1") (pin "15") (pinfunction "PA5_15") (pintype "bidirectional"))
    )
    (net (code "22") (name "/SPI2_CS_USB") (class "Default")
      (node (ref "R9") (pin "1") (pinfunction "1_1") (pintype "passive"))
      (node (ref "U2") (pin "5") (pinfunction "GP0_5") (pintype "bidirectional"))
    )
    (net (code "23") (name "/SPI2_CS_USB_R") (class "Default")
      (node (ref "R9") (pin "2") (pinfunction "2_2") (pintype "passive"))
      (node (ref "U1") (pin "25") (pinfunction "PB12_25") (pintype "bidirectional"))
    )
    (net (code "24") (name "/SPI2_MISO") (class "Default")
      (node (ref "R1") (pin "1") (pinfunction "1_1") (pintype "passive"))
      (node (ref "U1") (pin "27") (pinfunction "PB14_27") (pintype "bidirectional"))
    )
    (net (code "25") (name "/SPI2_MISO_R") (class "Default")
      (node (ref "R1") (pin "2") (pinfunction "2_2") (pintype "passive"))
      (node (ref "U2") (pin "13") (pinfunction "MISO_13") (pintype "input"))
    )
    (net (code "26") (name "/SPI2_MOSI") (class "Default")
      (node (ref "R12") (pin "1") (pinfunction "1_1") (pintype "passive"))
      (node (ref "U2") (pin "9") (pinfunction "MOSI_9") (pintype "output"))
    )
    (net (code "27") (name "/SPI2_MOSI_R") (class "Default")
      (node (ref "R12") (pin "2") (pinfunction "2_2") (pintype "passive"))
      (node (ref "U1") (pin "28") (pinfunction "PB15_28") (pintype "bidirectional"))
    )
    (net (code "28") (name "/SPI2_SCK") (class "Default")
      (node (ref "R10") (pin "1") (pinfunction "1_1") (pintype "passive"))
      (node (ref "U2") (pin "11") (pinfunction "SCK_11") (pintype "output"))
    )
    (net (code "29") (name "/SPI2_SCK_R") (class "Default")
      (node (ref "R10") (pin "2") (pinfunction "2_2") (pintype "passive"))
      (node (ref "U1") (pin "26") (pinfunction "PB13_26") (pintype "bidirectional"))
    )
    (net (code "30") (name "/SPI_ACK") (class "Default")
      (node (ref "U1") (pin "42") (pinfunction "PB6_42") (pintype "bidirectional"))
      (node (ref "U2") (pin "15") (pinfunction "GP7_15") (pintype "bidirectional"))
    )
    (net (code "31") (name "/SPI_REQ") (class "Default")
      (node (ref "U1") (pin "43") (pinfunction "PB7_43") (pintype "bidirectional"))
      (node (ref "U2") (pin "16") (pinfunction "GP8_16") (pintype "bidirectional"))
    )
    (net (code "32") (name "/SWD_CLK") (class "Default")
      (node (ref "P3") (pin "4") (pinfunction "4_4") (pintype "passive"))
      (node (ref "R7") (pin "2") (pinfunction "2_2") (pintype "passive"))
      (node (ref "U1") (pin "37") (pinfunction "PA14(SWCLK)_37") (pintype "bidirectional"))
    )
    (net (code "33") (name "/SWD_DIO") (class "Default")
      (node (ref "P3") (pin "2") (pinfunction "2_2") (pintype "passive"))
      (node (ref "R4") (pin "1") (pinfunction "1_1") (pintype "passive"))
      (node (ref "U1") (pin "34") (pinfunction "PA13(SWDIO)_34") (pintype "bidirectional"))
    )
    (net (code "34") (name "/T+") (class "Default")
      (node (ref "J3") (pin "4") (pinfunction "4_4") (pintype "passive"))
      (node (ref "L1") (pin "1") (pinfunction "1_1") (pintype "passive"))
    )
    (net (code "35") (name "/T-") (class "Default")
      (node (ref "J3") (pin "3") (pinfunction "3_3") (pintype "passive"))
      (node (ref "L2") (pin "1") (pinfunction "1_1") (pintype "passive"))
    )
    (net (code "36") (name "/UART_RX") (class "Default")
      (node (ref "P1") (pin "1") (pinfunction "1_1") (pintype "passive"))
      (node (ref "U1") (pin "31") (pinfunction "PA10_31") (pintype "bidirectional"))
    )
    (net (code "37") (name "/UART_TX") (class "Default")
      (node (ref "P1") (pin "2") (pinfunction "2_2") (pintype "passive"))
      (node (ref "U1") (pin "30") (pinfunction "PA9_30") (pintype "bidirectional"))
    )
    (net (code "38") (name "/USB_CONF") (class "Default")
      (node (ref "U1") (pin "40") (pinfunction "PB4_40") (pintype "bidirectional"))
      (node (ref "U2") (pin "12") (pinfunction "GP5_12") (pintype "bidirectional"))
    )
    (net (code "39") (name "/USB_LOWPWR") (class "Default")
      (node (ref "U1") (pin "39") (pinfunction "PB3_39") (pintype "bidirectional"))
      (node (ref "U2") (pin "10") (pinfunction "GP4_10") (pintype "bidirectional"))
    )
    (net (code "40") (name "/USB_N") (class "Default")
      (node (ref "P2") (pin "2") (pinfunction "2_2") (pintype "passive"))
      (node (ref "U2") (pin "18") (pinfunction "D-_18") (pintype "bidirectional"))
    )
    (net (code "41") (name "/USB_P") (class "Default")
      (node (ref "P2") (pin "3") (pinfunction "3_3") (pintype "passive"))
      (node (ref "U2") (pin "19") (pinfunction "D+_19") (pintype "bidirectional"))
    )
    (net (code "42") (name "/USB_SUSP") (class "Default")
      (node (ref "U1") (pin "20") (pinfunction "PB2_20") (pintype "bidirectional"))
      (node (ref "U2") (pin "7") (pinfunction "GP2_7") (pintype "bidirectional"))
    )
    (net (code "43") (name "/ZERO_DET") (class "Default")
      (node (ref "R16") (pin "2") (pinfunction "2_2") (pintype "passive"))
      (node (ref "U1") (pin "10") (pinfunction "PA0_10") (pintype "bidirectional"))
    )
    (net (code "44") (name "GND") (class "Default")
      (node (ref "C1") (pin "2") (pinfunction "2_2") (pintype "passive"))
      (node (ref "C10") (pin "2") (pinfunction "2_2") (pintype "passive"))
      (node (ref "C11") (pin "1") (pinfunction "C_1") (pintype "passive"))
      (node (ref "C12") (pin "2") (pinfunction "2_2") (pintype "passive"))
      (node (ref "C13") (pin "2") (pinfunction "2_2") (pintype "passive"))
      (node (ref "C14") (pin "1") (pinfunction "C_1") (pintype "passive"))
      (node (ref "C15") (pin "2") (pinfunction "2_2") (pintype "passive"))
      (node (ref "C16") (pin "1") (pinfunction "1_1") (pintype "passive"))
      (node (ref "C17") (pin "1") (pinfunction "1_1") (pintype "passive"))
      (node (ref "C18") (pin "2") (pinfunction "2_2") (pintype "passive"))
      (node (ref "C2") (pin "2") (pinfunction "2_2") (pintype "passive"))
      (node (ref "C20") (pin "2") (pinfunction "2_2") (pintype "passive"))
      (node (ref "C21") (pin "2") (pinfunction "2_2") (pintype "passive"))
      (node (ref "C23") (pin "2") (pinfunction "2_2") (pintype "passive"))
      (node (ref "C3") (pin "2") (pinfunction "2_2") (pintype "passive"))
      (node (ref "C4") (pin "2") (pinfunction "2_2") (pintype "passive"))
      (node (ref "C5") (pin "2") (pinfunction "2_2") (pintype "passive"))
      (node (ref "C6") (pin "2") (pinfunction "2_2") (pintype "passive"))
      (node (ref "C7") (pin "1") (pinfunction "1_1") (pintype "passive"))
      (node (ref "C8") (pin "1") (pinfunction "1_1") (pintype "passive"))
      (node (ref "C9") (pin "2") (pinfunction "2_2") (pintype "passive"))
      (node (ref "D1") (pin "2") (pinfunction "+_2") (pintype "passive"))
      (node (ref "D2") (pin "1") (pinfunction "C_1") (pintype "passive"))
      (node (ref "J5") (pin "2") (pinfunction "2_2") (pintype "passive"))
      (node (ref "J6") (pin "2") (pinfunction "2_2") (pintype "passive"))
      (node (ref "P2") (pin "4") (pinfunction "4_4") (pintype "passive"))
      (node (ref "P2") (pin "5") (pinfunction "5_5") (pintype "passive"))
      (node (ref "P3") (pin "3") (pinfunction "3_3") (pintype "passive"))
      (node (ref "P3") (pin "5") (pinfunction "5_5") (pintype "passive"))
      (node (ref "P3") (pin "7") (pinfunction "7_7") (pintype "passive"))
      (node (ref "P3") (pin "9") (pinfunction "9_9") (pintype "passive"))
      (node (ref "P4") (pin "4") (pinfunction "4_4") (pintype "passive"))
      (node (ref "P5") (pin "4") (pinfunction "4_4") (pintype "passive"))
      (node (ref "Q2") (pin "2") (pinfunction "C_2") (pintype "passive"))
      (node (ref "Q3") (pin "2") (pinfunction "C_2") (pintype "passive"))
      (node (ref "R13") (pin "2") (pinfunction "2_2") (pintype "passive"))
      (node (ref "R18") (pin "2") (pinfunction "2_2") (pintype "passive"))
      (node (ref "R24") (pin "1") (pinfunction "1_1") (pintype "passive"))
      (node (ref "R7") (pin "1") (pinfunction "1_1") (pintype "passive"))
      (node (ref "SW1") (pin "1") (pinfunction "1_1") (pintype "passive"))
      (node (ref "U1") (pin "23") (pinfunction "VSS_23") (pintype "power_in"))
      (node (ref "U1") (pin "47") (pinfunction "VSS_47") (pintype "power_in"))
      (node (ref "U1") (pin "8") (pinfunction "VSSA_8") (pintype "power_in"))
      (node (ref "U2") (pin "20") (pinfunction "VSS_20") (pintype "power_in"))
      (node (ref "U3") (pin "1") (pinfunction "GND_1") (pintype "power_in"))
      (node (ref "U4") (pin "1") (pinfunction "GND_1") (pintype "power_in"))
      (node (ref "VR1") (pin "1") (pinfunction "FIXED/ADJ_1") (pintype "input"))
    )
    (net (code "45") (name "Net-(C17-Pad2)") (class "Default")
      (node (ref "C17") (pin "2") (pinfunction "2_2") (pintype "passive"))
      (node (ref "R29") (pin "2") (pinfunction "2_2") (pintype "passive"))
      (node (ref "Y2") (pin "1") (pinfunction "1_1") (pintype "passive"))
    )
    (net (code "46") (name "Net-(D1-1_~)") (class "Default")
      (node (ref "D1") (pin "1") (pinfunction "1_~_1") (pintype "passive"))
      (node (ref "J1") (pin "1") (pinfunction "1_1") (pintype "passive"))
    )
    (net (code "47") (name "Net-(D1-2_~)") (class "Default")
      (node (ref "D1") (pin "4") (pinfunction "2_~_4") (pintype "passive"))
      (node (ref "J1") (pin "2") (pinfunction "2_2") (pintype "passive"))
    )
    (net (code "48") (name "Net-(D2-A)") (class "Default")
      (node (ref "D2") (pin "2") (pinfunction "A_2") (pintype "passive"))
      (node (ref "R8") (pin "1") (pinfunction "1_1") (pintype "passive"))
    )
    (net (code "49") (name "Net-(D3-G)") (class "Default")
      (node (ref "D3") (pin "3") (pinfunction "G_3") (pintype "passive"))
      (node (ref "Q3") (pin "4") (pinfunction "1_MAIN_TERM_4") (pintype "passive"))
    )
    (net (code "50") (name "Net-(D3-MT2)") (class "Default")
      (node (ref "D3") (pin "2") (pinfunction "MT2_2") (pintype "passive"))
      (node (ref "J3") (pin "1") (pinfunction "1_1") (pintype "passive"))
    )
    (net (code "51") (name "Net-(J4-Pad1)") (class "Default")
      (node (ref "J4") (pin "1") (pinfunction "1_1") (pintype "passive"))
      (node (ref "L4") (pin "1") (pinfunction "1_1") (pintype "passive"))
    )
    (net (code "52") (name "Net-(J4-Pad2)") (class "Default")
      (node (ref "J4") (pin "2") (pinfunction "2_2") (pintype "passive"))
      (node (ref "L3") (pin "1") (pinfunction "1_1") (pintype "passive"))
    )
    (net (code "53") (name "Net-(Q1-B)") (class "Default")
      (node (ref "Q1") (pin "1") (pinfunction "B_1") (pintype "passive"))
      (node (ref "R3") (pin "1") (pinfunction "1_1") (pintype "passive"))
    )
    (net (code "54") (name "Net-(Q1-E)") (class "Default")
      (node (ref "Q1") (pin "2") (pinfunction "E_2") (pintype "passive"))
      (node (ref "R8") (pin "2") (pinfunction "2_2") (pintype "passive"))
    )
    (net (code "55") (name "Net-(Q2-A)") (class "Default")
      (node (ref "Q2") (pin "1") (pinfunction "A_1") (pintype "passive"))
      (node (ref "R14") (pin "1") (pinfunction "1_1") (pintype "passive"))
    )
    (net (code "56") (name "Net-(Q2-E)") (class "Default")
      (node (ref "Q2") (pin "3") (pinfunction "E_3") (pintype "passive"))
      (node (ref "R16") (pin "1") (pinfunction "1_1") (pintype "passive"))
      (node (ref "R18") (pin "1") (pinfunction "1_1") (pintype "passive"))
    )
    (net (code "57") (name "Net-(Q3-2_MAIN_TERM)") (class "Default")
      (node (ref "Q3") (pin "6") (pinfunction "2_MAIN_TERM_6") (pintype "passive"))
      (node (ref "R20") (pin "2") (pinfunction "2_2") (pintype "passive"))
    )
    (net (code "58") (name "Net-(Q3-A)") (class "Default")
      (node (ref "Q3") (pin "1") (pinfunction "A_1") (pintype "passive"))
      (node (ref "R19") (pin "1") (pinfunction "1_1") (pintype "passive"))
    )
    (net (code "59") (name "Net-(Q4-B)") (class "Default")
      (node (ref "Q4") (pin "1") (pinfunction "B_1") (pintype "passive"))
      (node (ref "R26") (pin "1") (pinfunction "1_1") (pintype "passive"))
    )
    (net (code "60") (name "Net-(Q4-E)") (class "Default")
      (node (ref "Q4") (pin "2") (pinfunction "E_2") (pintype "passive"))
      (node (ref "Q5") (pin "1") (pinfunction "B_1") (pintype "passive"))
    )
    (net (code "61") (name "Net-(Q5-E)") (class "Default")
      (node (ref "J5") (pin "1") (pinfunction "1_1") (pintype "passive"))
      (node (ref "Q5") (pin "3") (pinfunction "E_3") (pintype "passive"))
    )
    (net (code "62") (name "Net-(Q6-B)") (class "Default")
      (node (ref "Q6") (pin "1") (pinfunction "B_1") (pintype "passive"))
      (node (ref "R27") (pin "1") (pinfunction "1_1") (pintype "passive"))
    )
    (net (code "63") (name "Net-(Q6-E)") (class "Default")
      (node (ref "Q6") (pin "2") (pinfunction "E_2") (pintype "passive"))
      (node (ref "Q7") (pin "1") (pinfunction "B_1") (pintype "passive"))
    )
    (net (code "64") (name "Net-(Q7-E)") (class "Default")
      (node (ref "J6") (pin "1") (pinfunction "1_1") (pintype "passive"))
      (node (ref "Q7") (pin "3") (pinfunction "E_3") (pintype "passive"))
    )
    (net (code "65") (name "Net-(U1A-BOOT0)") (class "Default")
      (node (ref "R13") (pin "1") (pinfunction "1_1") (pintype "passive"))
      (node (ref "U1") (pin "44") (pinfunction "BOOT0_44") (pintype "input"))
    )
    (net (code "66") (name "Net-(U1A-NRST)") (class "Default")
      (node (ref "C18") (pin "1") (pinfunction "1_1") (pintype "passive"))
      (node (ref "R15") (pin "1") (pinfunction "1_1") (pintype "passive"))
      (node (ref "R17") (pin "1") (pinfunction "1_1") (pintype "passive"))
      (node (ref "U1") (pin "7") (pinfunction "NRST_7") (pintype "bidirectional"))
    )
    (net (code "67") (name "Net-(U1A-PF0-OSC_IN(PF0))") (class "Default")
      (node (ref "C16") (pin "2") (pinfunction "2_2") (pintype "passive"))
      (node (ref "U1") (pin "5") (pinfunction "PF0-OSC_IN(PF0)_5") (pintype "bidirectional"))
      (node (ref "Y2") (pin "2") (pinfunction "2_2") (pintype "passive"))
    )
    (net (code "68") (name "Net-(U1A-PF1-OSC_OUT(PF1))") (class "Default")
      (node (ref "R29") (pin "1") (pinfunction "1_1") (pintype "passive"))
      (node (ref "U1") (pin "6") (pinfunction "PF1-OSC_OUT(PF1)_6") (pintype "bidirectional"))
    )
    (net (code "69") (name "Net-(U2-GP3)") (class "Default")
      (node (ref "R3") (pin "2") (pinfunction "2_2") (pintype "passive"))
      (node (ref "U2") (pin "8") (pinfunction "GP3_8") (pintype "bidirectional"))
    )
    (net (code "70") (name "Net-(U2-OSC1)") (class "Default")
      (node (ref "C7") (pin "2") (pinfunction "2_2") (pintype "passive"))
      (node (ref "U2") (pin "2") (pinfunction "OSC1_2") (pintype "input"))
      (node (ref "Y1") (pin "2") (pinfunction "2_2") (pintype "passive"))
    )
    (net (code "71") (name "Net-(U2-OSC2)") (class "Default")
      (node (ref "C8") (pin "2") (pinfunction "2_2") (pintype "passive"))
      (node (ref "U2") (pin "3") (pinfunction "OSC2_3") (pintype "output"))
      (node (ref "Y1") (pin "1") (pinfunction "1_1") (pintype "passive"))
    )
    (net (code "72") (name "Net-(U2-~{RST})") (class "Default")
      (node (ref "R2") (pin "2") (pinfunction "2_2") (pintype "passive"))
      (node (ref "U2") (pin "4") (pinfunction "~{RST}_4") (pintype "input"))
    )
    (net (code "73") (name "Net-(U3-T+)") (class "Default")
      (node (ref "C19") (pin "1") (pinfunction "1_1") (pintype "passive"))
      (node (ref "L1") (pin "2") (pinfunction "2_2") (pintype "passive"))
      (node (ref "U3") (pin "3") (pinfunction "T+_3") (pintype "input"))
    )
    (net (code "74") (name "Net-(U3-T-)") (class "Default")
      (node (ref "C19") (pin "2") (pinfunction "2_2") (pintype "passive"))
      (node (ref "L2") (pin "2") (pinfunction "2_2") (pintype "passive"))
      (node (ref "U3") (pin "2") (pinfunction "T-_2") (pintype "input"))
    )
    (net (code "75") (name "Net-(U4-T+)") (class "Default")
      (node (ref "C22") (pin "1") (pinfunction "1_1") (pintype "passive"))
      (node (ref "L3") (pin "2") (pinfunction "2_2") (pintype "passive"))
      (node (ref "U4") (pin "3") (pinfunction "T+_3") (pintype "input"))
    )
    (net (code "76") (name "Net-(U4-T-)") (class "Default")
      (node (ref "C22") (pin "2") (pinfunction "2_2") (pintype "passive"))
      (node (ref "L4") (pin "2") (pinfunction "2_2") (pintype "passive"))
      (node (ref "U4") (pin "2") (pinfunction "T-_2") (pintype "input"))
    )
    (net (code "77") (name "unconnected-(J1-Pad3)") (class "Default")
      (node (ref "J1") (pin "3") (pinfunction "3_3") (pintype "passive+no_connect"))
    )
    (net (code "78") (name "unconnected-(J1-Pad4)") (class "Default")
      (node (ref "J1") (pin "4") (pinfunction "4_4") (pintype "passive+no_connect"))
    )
    (net (code "79") (name "unconnected-(J1-Pad5)") (class "Default")
      (node (ref "J1") (pin "5") (pinfunction "5_5") (pintype "passive+no_connect"))
    )
    (net (code "80") (name "unconnected-(P2-Pad1)") (class "Default")
      (node (ref "P2") (pin "1") (pinfunction "1_1") (pintype "passive+no_connect"))
    )
    (net (code "81") (name "unconnected-(P3-Pad6)") (class "Default")
      (node (ref "P3") (pin "6") (pinfunction "6_6") (pintype "passive"))
    )
    (net (code "82") (name "unconnected-(P3-Pad8)") (class "Default")
      (node (ref "P3") (pin "8") (pinfunction "8_8") (pintype "passive"))
    )
    (net (code "83") (name "unconnected-(Q3-NC-Pad3)") (class "Default")
      (node (ref "Q3") (pin "3") (pinfunction "NC_3") (pintype "passive+no_connect"))
    )
    (net (code "84") (name "unconnected-(Q3-NC-Pad5)") (class "Default")
      (node (ref "Q3") (pin "5") (pinfunction "NC_5") (pintype "passive+no_connect"))
    )
    (net (code "85") (name "unconnected-(U1A-PA3-Pad13)") (class "Default")
      (node (ref "U1") (pin "13") (pinfunction "PA3_13") (pintype "bidirectional"))
    )
    (net (code "86") (name "unconnected-(U1A-PA7-Pad17)") (class "Default")
      (node (ref "U1") (pin "17") (pinfunction "PA7_17") (pintype "bidirectional"))
    )
    (net (code "87") (name "unconnected-(U1A-PA8-Pad29)") (class "Default")
      (node (ref "U1") (pin "29") (pinfunction "PA8_29") (pintype "bidirectional"))
    )
    (net (code "88") (name "unconnected-(U1A-PA11-Pad32)") (class "Default")
      (node (ref "U1") (pin "32") (pinfunction "PA11_32") (pintype "bidirectional"))
    )
    (net (code "89") (name "unconnected-(U1A-PA12-Pad33)") (class "Default")
      (node (ref "U1") (pin "33") (pinfunction "PA12_33") (pintype "bidirectional"))
    )
    (net (code "90") (name "unconnected-(U1A-PC13-Pad2)") (class "Default")
      (node (ref "U1") (pin "2") (pinfunction "PC13_2") (pintype "bidirectional"))
    )
    (net (code "91") (name "unconnected-(U1A-PC14-OSC32_IN(PC14)-Pad3)") (class "Default")
      (node (ref "U1") (pin "3") (pinfunction "PC14-OSC32_IN(PC14)_3") (pintype "bidirectional"))
    )
    (net (code "92") (name "unconnected-(U1A-PC15-OSC32_OUT(PC15)-Pad4)") (class "Default")
      (node (ref "U1") (pin "4") (pinfunction "PC15-OSC32_OUT(PC15)_4") (pintype "bidirectional"))
    )
    (net (code "93") (name "unconnected-(U1A-PF6-Pad35)") (class "Default")
      (node (ref "U1") (pin "35") (pinfunction "PF6_35") (pintype "bidirectional"))
    )
    (net (code "94") (name "unconnected-(U1A-PF7-Pad36)") (class "Default")
      (node (ref "U1") (pin "36") (pinfunction "PF7_36") (pintype "bidirectional"))
    )
    (net (code "95") (name "unconnected-(U2-GP1-Pad6)") (class "Default")
      (node (ref "U2") (pin "6") (pinfunction "GP1_6") (pintype "bidirectional"))
    )
    (net (code "96") (name "unconnected-(U3-DNC-Pad8)") (class "Default")
      (node (ref "U3") (pin "8") (pinfunction "DNC_8") (pintype "passive"))
    )
    (net (code "97") (name "unconnected-(U4-DNC-Pad8)") (class "Default")
      (node (ref "U4") (pin "8") (pinfunction "DNC_8") (pintype "passive"))
    )
    (net (code "98") (name "~230") (class "Default")
      (node (ref "D3") (pin "1") (pinfunction "MT1_1") (pintype "passive"))
      (node (ref "J2") (pin "1") (pinfunction "1_1") (pintype "passive"))
      (node (ref "J2") (pin "2") (pinfunction "2_2") (pintype "passive"))
      (node (ref "R20") (pin "1") (pinfunction "1_1") (pintype "passive"))
      (node (ref "R28") (pin "2") (pinfunction "2_2") (pintype "passive"))
    )
    (net (code "99") (name "~N") (class "Default")
      (node (ref "J2") (pin "3") (pinfunction "3_3") (pintype "passive"))
      (node (ref "J2") (pin "4") (pinfunction "4_4") (pintype "passive"))
      (node (ref "J3") (pin "2") (pinfunction "2_2") (pintype "passive"))
      (node (ref "R28") (pin "1") (pinfunction "1_1") (pintype "passive"))
    )
  )
)
